# CMoy-Pro-Battery_Holder-V_1_0_0_1a.net
KiCad netlist of a schematic drawn in EAGLE
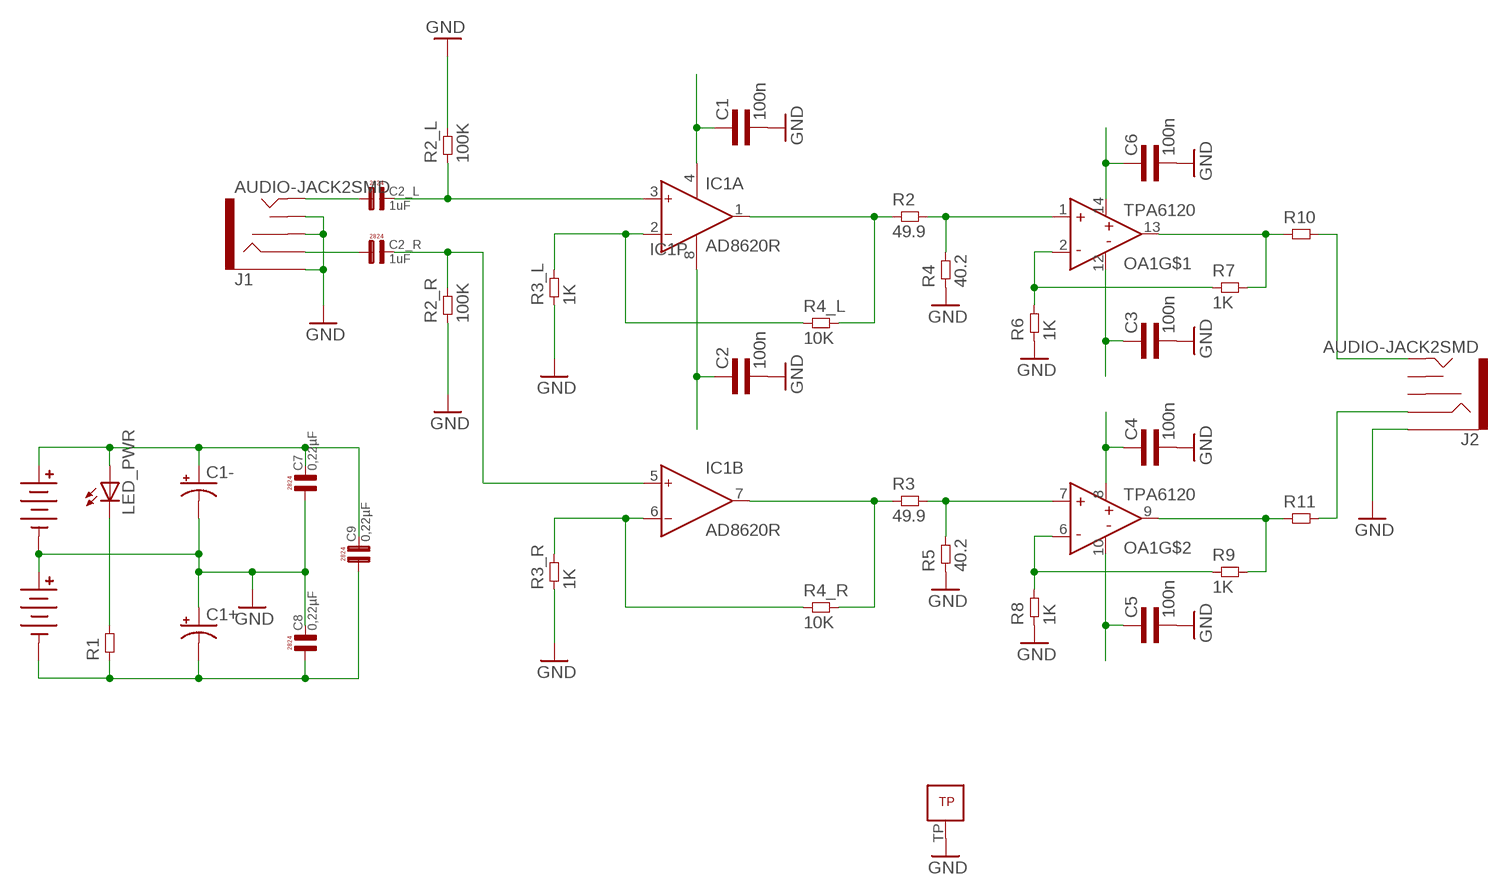
[diagram p0: schematic, sheet 1]

(export (version "E")
  (design (tool "Eeschema 10.0.6"))
  (components
    (comp (ref "BATT1")
      (value "BATT_9V")
      (footprint "eagle-import:9V_FEMALE")
      (libsource (lib "eagle-import") (part "BATT_9V"))
    )
    (comp (ref "BATT2")
      (value "BATT_9V")
      (footprint "eagle-import:9V_FEMALE")
      (libsource (lib "eagle-import") (part "BATT_9V"))
    )
    (comp (ref "C1")
      (value "100n")
      (footprint "eagle-import:0603L3")
      (libsource (lib "eagle-import") (part "CAP0603L3"))
    )
    (comp (ref "C1+")
      (value "CPOL-US140CLH-1010")
      (footprint "eagle-import:140CLH-1010")
      (libsource (lib "eagle-import") (part "CPOL-US140CLH-1010"))
    )
    (comp (ref "C1-")
      (value "CPOL-US140CLH-1010")
      (footprint "eagle-import:140CLH-1010")
      (libsource (lib "eagle-import") (part "CPOL-US140CLH-1010"))
    )
    (comp (ref "C2")
      (value "100n")
      (footprint "eagle-import:0603L3")
      (libsource (lib "eagle-import") (part "CAP0603L3"))
    )
    (comp (ref "C2_L")
      (value "1uF")
      (footprint "eagle-import:L7,2")
      (libsource (lib "eagle-import") (part "1,0µF"))
    )
    (comp (ref "C2_R")
      (value "1uF")
      (footprint "eagle-import:L7,2")
      (libsource (lib "eagle-import") (part "1,0µF"))
    )
    (comp (ref "C3")
      (value "100n")
      (footprint "eagle-import:0603L3")
      (libsource (lib "eagle-import") (part "CAP0603L3"))
    )
    (comp (ref "C4")
      (value "100n")
      (footprint "eagle-import:0603L3")
      (libsource (lib "eagle-import") (part "CAP0603L3"))
    )
    (comp (ref "C5")
      (value "100n")
      (footprint "eagle-import:0603L3")
      (libsource (lib "eagle-import") (part "CAP0603L3"))
    )
    (comp (ref "C6")
      (value "100n")
      (footprint "eagle-import:0603L3")
      (libsource (lib "eagle-import") (part "CAP0603L3"))
    )
    (comp (ref "C7")
      (value "0,22µF")
      (footprint "eagle-import:L7,2")
      (libsource (lib "eagle-import") (part "0,22µF"))
    )
    (comp (ref "C8")
      (value "0,22µF")
      (footprint "eagle-import:L7,2")
      (libsource (lib "eagle-import") (part "0,22µF"))
    )
    (comp (ref "C9")
      (value "0,22µF")
      (footprint "eagle-import:L7,2")
      (libsource (lib "eagle-import") (part "0,22µF"))
    )
    (comp (ref "IC1")
      (value "AD8620R")
      (footprint "eagle-import:SO8")
      (fields (field (name "MF") "ALTERA CORPORATION") (field (name "MPN") "AD8620ARZ"))
      (libsource (lib "eagle-import") (part "AD8620R"))
    )
    (comp (ref "J1")
      (value "AUDIO-JACK2SMD")
      (footprint "eagle-import:AUDIO-JACK-3.5MM-SMD")
      (libsource (lib "eagle-import") (part "AUDIO-JACK2SMD"))
    )
    (comp (ref "J2")
      (value "AUDIO-JACK2SMD")
      (footprint "eagle-import:AUDIO-JACK-3.5MM-SMD")
      (libsource (lib "eagle-import") (part "AUDIO-JACK2SMD"))
    )
    (comp (ref "LED_PWR")
      (value "LEDCHIP-LED0603")
      (footprint "eagle-import:CHIP-LED0603")
      (libsource (lib "eagle-import") (part "LEDCHIP-LED0603"))
    )
    (comp (ref "OA1")
      (value "TPA6120QFN")
      (footprint "eagle-import:S-PVQFN-N14")
      (libsource (lib "eagle-import") (part "TPA6120QFN"))
    )
    (comp (ref "R1")
      (value "RES0603L3")
      (footprint "eagle-import:0603L3")
      (libsource (lib "eagle-import") (part "RES0603L3"))
    )
    (comp (ref "R2")
      (value "49.9")
      (footprint "eagle-import:0603L3")
      (libsource (lib "eagle-import") (part "RES0603L3"))
    )
    (comp (ref "R2_L")
      (value "100K")
      (footprint "eagle-import:0603L3")
      (libsource (lib "eagle-import") (part "RES0603L3"))
    )
    (comp (ref "R2_R")
      (value "100K")
      (footprint "eagle-import:0603L3")
      (libsource (lib "eagle-import") (part "RES0603L3"))
    )
    (comp (ref "R3")
      (value "49.9")
      (footprint "eagle-import:0603L3")
      (libsource (lib "eagle-import") (part "RES0603L3"))
    )
    (comp (ref "R3_L")
      (value "1K")
      (footprint "eagle-import:0603L3")
      (libsource (lib "eagle-import") (part "RES0603L3"))
    )
    (comp (ref "R3_R")
      (value "1K")
      (footprint "eagle-import:0603L3")
      (libsource (lib "eagle-import") (part "RES0603L3"))
    )
    (comp (ref "R4")
      (value "40.2")
      (footprint "eagle-import:0603L3")
      (libsource (lib "eagle-import") (part "RES0603L3"))
    )
    (comp (ref "R4_L")
      (value "10K")
      (footprint "eagle-import:0603L3")
      (libsource (lib "eagle-import") (part "RES0603L3"))
    )
    (comp (ref "R4_R")
      (value "10K")
      (footprint "eagle-import:0603L3")
      (libsource (lib "eagle-import") (part "RES0603L3"))
    )
    (comp (ref "R5")
      (value "40.2")
      (footprint "eagle-import:0603L3")
      (libsource (lib "eagle-import") (part "RES0603L3"))
    )
    (comp (ref "R6")
      (value "1K")
      (footprint "eagle-import:0603L3")
      (libsource (lib "eagle-import") (part "RES0603L3"))
    )
    (comp (ref "R7")
      (value "1K")
      (footprint "eagle-import:0603L3")
      (libsource (lib "eagle-import") (part "RES0603L3"))
    )
    (comp (ref "R8")
      (value "1K")
      (footprint "eagle-import:0603L3")
      (libsource (lib "eagle-import") (part "RES0603L3"))
    )
    (comp (ref "R9")
      (value "1K")
      (footprint "eagle-import:0603L3")
      (libsource (lib "eagle-import") (part "RES0603L3"))
    )
    (comp (ref "R10")
      (value "RES1206L3")
      (footprint "eagle-import:1206L3")
      (libsource (lib "eagle-import") (part "RES1206L3"))
    )
    (comp (ref "R11")
      (value "RES1206L3")
      (footprint "eagle-import:1206L3")
      (libsource (lib "eagle-import") (part "RES1206L3"))
    )
  )
  (nets
    (net (code "1") (name "/V+") (class "Default")
      (node (ref "BATT1") (pin "P1") (pinfunction "POS_P1") (pintype "bidirectional"))
      (node (ref "BATT1") (pin "P2") (pinfunction "POS_P2") (pintype "bidirectional"))
      (node (ref "BATT1") (pin "P3") (pinfunction "POS_P3") (pintype "bidirectional"))
      (node (ref "C1-") (pin "+") (pinfunction "+_+") (pintype "passive"))
      (node (ref "C2") (pin "P$1") (pinfunction "1_P$1") (pintype "bidirectional"))
      (node (ref "C4") (pin "P$1") (pinfunction "1_P$1") (pintype "bidirectional"))
      (node (ref "C6") (pin "P$1") (pinfunction "1_P$1") (pintype "bidirectional"))
      (node (ref "C7") (pin "P$2") (pinfunction "2_P$2") (pintype "passive"))
      (node (ref "C9") (pin "P$2") (pinfunction "2_P$2") (pintype "passive"))
      (node (ref "IC1") (pin "8") (pinfunction "V+_8") (pintype "power_in"))
      (node (ref "LED_PWR") (pin "A") (pinfunction "A_A") (pintype "passive"))
      (node (ref "OA1") (pin "14") (pinfunction "V+_14") (pintype "bidirectional"))
      (node (ref "OA1") (pin "8") (pinfunction "V+_8") (pintype "bidirectional"))
    )
    (net (code "2") (name "/V-") (class "Default")
      (node (ref "BATT2") (pin "N1") (pinfunction "NEG_N1") (pintype "bidirectional"))
      (node (ref "BATT2") (pin "N2") (pinfunction "NEG_N2") (pintype "bidirectional"))
      (node (ref "BATT2") (pin "N3") (pinfunction "NEG_N3") (pintype "bidirectional"))
      (node (ref "C1") (pin "P$1") (pinfunction "1_P$1") (pintype "bidirectional"))
      (node (ref "C1+") (pin "-") (pinfunction "-_-") (pintype "passive"))
      (node (ref "C3") (pin "P$1") (pinfunction "1_P$1") (pintype "bidirectional"))
      (node (ref "C5") (pin "P$1") (pinfunction "1_P$1") (pintype "bidirectional"))
      (node (ref "C8") (pin "P$1") (pinfunction "1_P$1") (pintype "passive"))
      (node (ref "C9") (pin "P$1") (pinfunction "1_P$1") (pintype "passive"))
      (node (ref "IC1") (pin "4") (pinfunction "V-_4") (pintype "power_in"))
      (node (ref "OA1") (pin "10") (pinfunction "V-_10") (pintype "bidirectional"))
      (node (ref "OA1") (pin "12") (pinfunction "V-_12") (pintype "bidirectional"))
      (node (ref "R1") (pin "P$1") (pinfunction "1_P$1") (pintype "bidirectional"))
    )
    (net (code "3") (name "GND") (class "Default")
      (node (ref "BATT1") (pin "N1") (pinfunction "NEG_N1") (pintype "bidirectional"))
      (node (ref "BATT1") (pin "N2") (pinfunction "NEG_N2") (pintype "bidirectional"))
      (node (ref "BATT1") (pin "N3") (pinfunction "NEG_N3") (pintype "bidirectional"))
      (node (ref "BATT2") (pin "P1") (pinfunction "POS_P1") (pintype "bidirectional"))
      (node (ref "BATT2") (pin "P2") (pinfunction "POS_P2") (pintype "bidirectional"))
      (node (ref "BATT2") (pin "P3") (pinfunction "POS_P3") (pintype "bidirectional"))
      (node (ref "C1") (pin "P$2") (pinfunction "2_P$2") (pintype "bidirectional"))
      (node (ref "C1+") (pin "+") (pinfunction "+_+") (pintype "passive"))
      (node (ref "C1-") (pin "-") (pinfunction "-_-") (pintype "passive"))
      (node (ref "C2") (pin "P$2") (pinfunction "2_P$2") (pintype "bidirectional"))
      (node (ref "C3") (pin "P$2") (pinfunction "2_P$2") (pintype "bidirectional"))
      (node (ref "C4") (pin "P$2") (pinfunction "2_P$2") (pintype "bidirectional"))
      (node (ref "C5") (pin "P$2") (pinfunction "2_P$2") (pintype "bidirectional"))
      (node (ref "C6") (pin "P$2") (pinfunction "2_P$2") (pintype "bidirectional"))
      (node (ref "C7") (pin "P$1") (pinfunction "1_P$1") (pintype "passive"))
      (node (ref "C8") (pin "P$2") (pinfunction "2_P$2") (pintype "passive"))
      (node (ref "J1") (pin "RSH") (pinfunction "RSH_RSH") (pintype "bidirectional"))
      (node (ref "J1") (pin "SLEEVE") (pinfunction "SLEEVE_SLEEVE") (pintype "bidirectional"))
      (node (ref "J1") (pin "TSH") (pinfunction "TSH_TSH") (pintype "bidirectional"))
      (node (ref "J2") (pin "SLEEVE") (pinfunction "SLEEVE_SLEEVE") (pintype "bidirectional"))
      (node (ref "OA1") (pin "TP") (pinfunction "TP_TP") (pintype "bidirectional"))
      (node (ref "R2_L") (pin "P$2") (pinfunction "2_P$2") (pintype "bidirectional"))
      (node (ref "R2_R") (pin "P$1") (pinfunction "1_P$1") (pintype "bidirectional"))
      (node (ref "R3_L") (pin "P$1") (pinfunction "1_P$1") (pintype "bidirectional"))
      (node (ref "R3_R") (pin "P$1") (pinfunction "1_P$1") (pintype "bidirectional"))
      (node (ref "R4") (pin "P$1") (pinfunction "1_P$1") (pintype "bidirectional"))
      (node (ref "R5") (pin "P$1") (pinfunction "1_P$1") (pintype "bidirectional"))
      (node (ref "R6") (pin "P$1") (pinfunction "1_P$1") (pintype "bidirectional"))
      (node (ref "R8") (pin "P$1") (pinfunction "1_P$1") (pintype "bidirectional"))
    )
    (net (code "4") (name "Net-(C2_L-1)") (class "Default")
      (node (ref "C2_L") (pin "P$1") (pinfunction "1_P$1") (pintype "passive"))
      (node (ref "J1") (pin "TIP") (pinfunction "TIP_TIP") (pintype "bidirectional"))
    )
    (net (code "5") (name "Net-(C2_L-2)") (class "Default")
      (node (ref "C2_L") (pin "P$2") (pinfunction "2_P$2") (pintype "passive"))
      (node (ref "IC1") (pin "3") (pinfunction "IN+_3") (pintype "input"))
      (node (ref "R2_L") (pin "P$1") (pinfunction "1_P$1") (pintype "bidirectional"))
    )
    (net (code "6") (name "Net-(C2_R-1)") (class "Default")
      (node (ref "C2_R") (pin "P$1") (pinfunction "1_P$1") (pintype "passive"))
      (node (ref "J1") (pin "RING") (pinfunction "RING_RING") (pintype "bidirectional"))
    )
    (net (code "7") (name "Net-(C2_R-2)") (class "Default")
      (node (ref "C2_R") (pin "P$2") (pinfunction "2_P$2") (pintype "passive"))
      (node (ref "IC1") (pin "5") (pinfunction "IN+_5") (pintype "input"))
      (node (ref "R2_R") (pin "P$2") (pinfunction "2_P$2") (pintype "bidirectional"))
    )
    (net (code "8") (name "Net-(IC1A-IN-)") (class "Default")
      (node (ref "IC1") (pin "2") (pinfunction "IN-_2") (pintype "input"))
      (node (ref "R3_L") (pin "P$2") (pinfunction "2_P$2") (pintype "bidirectional"))
      (node (ref "R4_L") (pin "P$1") (pinfunction "1_P$1") (pintype "bidirectional"))
    )
    (net (code "9") (name "Net-(IC1A-OUT)") (class "Default")
      (node (ref "IC1") (pin "1") (pinfunction "OUT_1") (pintype "output"))
      (node (ref "R2") (pin "P$1") (pinfunction "1_P$1") (pintype "bidirectional"))
      (node (ref "R4_L") (pin "P$2") (pinfunction "2_P$2") (pintype "bidirectional"))
    )
    (net (code "10") (name "Net-(IC1B-IN-)") (class "Default")
      (node (ref "IC1") (pin "6") (pinfunction "IN-_6") (pintype "input"))
      (node (ref "R3_R") (pin "P$2") (pinfunction "2_P$2") (pintype "bidirectional"))
      (node (ref "R4_R") (pin "P$1") (pinfunction "1_P$1") (pintype "bidirectional"))
    )
    (net (code "11") (name "Net-(IC1B-OUT)") (class "Default")
      (node (ref "IC1") (pin "7") (pinfunction "OUT_7") (pintype "output"))
      (node (ref "R3") (pin "P$1") (pinfunction "1_P$1") (pintype "bidirectional"))
      (node (ref "R4_R") (pin "P$2") (pinfunction "2_P$2") (pintype "bidirectional"))
    )
    (net (code "12") (name "Net-(J2-PadRING)") (class "Default")
      (node (ref "J2") (pin "RING") (pinfunction "RING_RING") (pintype "bidirectional"))
      (node (ref "R11") (pin "2") (pinfunction "2_2") (pintype "bidirectional"))
    )
    (net (code "13") (name "Net-(J2-PadTIP)") (class "Default")
      (node (ref "J2") (pin "TIP") (pinfunction "TIP_TIP") (pintype "bidirectional"))
      (node (ref "R10") (pin "2") (pinfunction "2_2") (pintype "bidirectional"))
    )
    (net (code "14") (name "Net-(OA1A-IN+)") (class "Default")
      (node (ref "OA1") (pin "1") (pinfunction "IN+_1") (pintype "bidirectional"))
      (node (ref "R2") (pin "P$2") (pinfunction "2_P$2") (pintype "bidirectional"))
      (node (ref "R4") (pin "P$2") (pinfunction "2_P$2") (pintype "bidirectional"))
    )
    (net (code "15") (name "Net-(OA1A-IN-)") (class "Default")
      (node (ref "OA1") (pin "2") (pinfunction "IN-_2") (pintype "bidirectional"))
      (node (ref "R6") (pin "P$2") (pinfunction "2_P$2") (pintype "bidirectional"))
      (node (ref "R7") (pin "P$1") (pinfunction "1_P$1") (pintype "bidirectional"))
    )
    (net (code "16") (name "Net-(OA1A-OUT)") (class "Default")
      (node (ref "OA1") (pin "13") (pinfunction "OUT_13") (pintype "bidirectional"))
      (node (ref "R10") (pin "1") (pinfunction "1_1") (pintype "bidirectional"))
      (node (ref "R7") (pin "P$2") (pinfunction "2_P$2") (pintype "bidirectional"))
    )
    (net (code "17") (name "Net-(OA1B-IN+)") (class "Default")
      (node (ref "OA1") (pin "7") (pinfunction "IN+_7") (pintype "bidirectional"))
      (node (ref "R3") (pin "P$2") (pinfunction "2_P$2") (pintype "bidirectional"))
      (node (ref "R5") (pin "P$2") (pinfunction "2_P$2") (pintype "bidirectional"))
    )
    (net (code "18") (name "Net-(OA1B-IN-)") (class "Default")
      (node (ref "OA1") (pin "6") (pinfunction "IN-_6") (pintype "bidirectional"))
      (node (ref "R8") (pin "P$2") (pinfunction "2_P$2") (pintype "bidirectional"))
      (node (ref "R9") (pin "P$1") (pinfunction "1_P$1") (pintype "bidirectional"))
    )
    (net (code "19") (name "Net-(OA1B-OUT)") (class "Default")
      (node (ref "OA1") (pin "9") (pinfunction "OUT_9") (pintype "bidirectional"))
      (node (ref "R11") (pin "1") (pinfunction "1_1") (pintype "bidirectional"))
      (node (ref "R9") (pin "P$2") (pinfunction "2_P$2") (pintype "bidirectional"))
    )
    (net (code "20") (name "Net-(R1-2)") (class "Default")
      (node (ref "LED_PWR") (pin "C") (pinfunction "C_C") (pintype "passive"))
      (node (ref "R1") (pin "P$2") (pinfunction "2_P$2") (pintype "bidirectional"))
    )
    (net (code "21") (name "unconnected-(J2-PadRSH)") (class "Default")
      (node (ref "J2") (pin "RSH") (pinfunction "RSH_RSH") (pintype "bidirectional"))
    )
    (net (code "22") (name "unconnected-(J2-PadTSH)") (class "Default")
      (node (ref "J2") (pin "TSH") (pinfunction "TSH_TSH") (pintype "bidirectional"))
    )
  )
)
